# pixel-clock.net
KiCad netlist of a schematic drawn in EAGLE
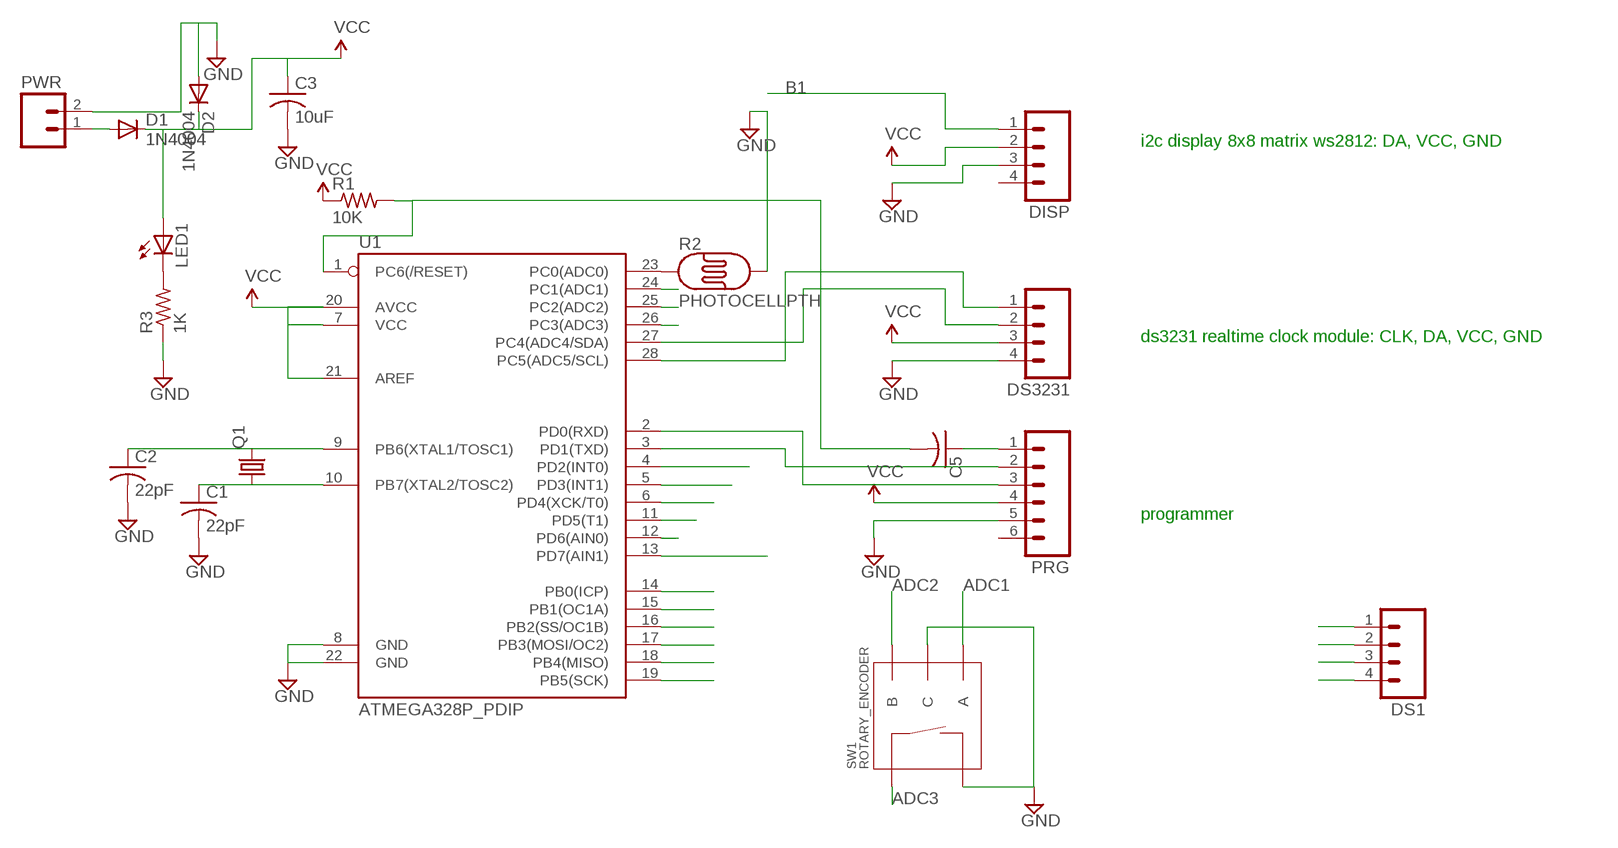
[diagram p0: schematic, sheet 1]

(export (version "E")
  (design (tool "Eeschema 10.0.6"))
  (components
    (comp (ref "C1")
      (value "22pF")
      (footprint "eagle-import:C050-024X044")
      (libsource (lib "eagle-import") (part "C-US050-024X044"))
    )
    (comp (ref "C2")
      (value "22pF")
      (footprint "eagle-import:C050-024X044")
      (libsource (lib "eagle-import") (part "C-US050-024X044"))
    )
    (comp (ref "C3")
      (value "10uF")
      (footprint "eagle-import:C025-025X050")
      (libsource (lib "eagle-import") (part "C-US025-025X050"))
    )
    (comp (ref "C5")
      (value "C-US025-025X050")
      (footprint "eagle-import:C025-025X050")
      (libsource (lib "eagle-import") (part "C-US025-025X050"))
    )
    (comp (ref "D1")
      (value "1N4004")
      (footprint "eagle-import:DO41-10")
      (libsource (lib "eagle-import") (part "1N4004"))
    )
    (comp (ref "D2")
      (value "1N4004")
      (footprint "eagle-import:DO41-10")
      (libsource (lib "eagle-import") (part "1N4004"))
    )
    (comp (ref "DISP")
      (value "M04PTH")
      (footprint "eagle-import:1X04")
      (libsource (lib "eagle-import") (part "M04PTH"))
    )
    (comp (ref "DS1")
      (value "M04PTH")
      (footprint "eagle-import:1X04")
      (libsource (lib "eagle-import") (part "M04PTH"))
    )
    (comp (ref "DS3231")
      (value "M04PTH")
      (footprint "eagle-import:1X04")
      (libsource (lib "eagle-import") (part "M04PTH"))
    )
    (comp (ref "LED1")
      (value "LED3MM")
      (footprint "eagle-import:LED3MM")
      (libsource (lib "eagle-import") (part "LED3MM"))
    )
    (comp (ref "PRG")
      (value "M06SILK_FEMALE_PTH")
      (footprint "eagle-import:1X06")
      (libsource (lib "eagle-import") (part "M06SILK_FEMALE_PTH"))
    )
    (comp (ref "PWR")
      (value "M02PTH3")
      (footprint "eagle-import:1X02_LONGPADS")
      (libsource (lib "eagle-import") (part "M02PTH3"))
    )
    (comp (ref "Q1")
      (value "CRYSTALHC49S")
      (footprint "eagle-import:HC49_S")
      (libsource (lib "eagle-import") (part "CRYSTALHC49S"))
    )
    (comp (ref "R1")
      (value "10K")
      (footprint "eagle-import:0207_9")
      (libsource (lib "eagle-import") (part "R-US_0207/9"))
    )
    (comp (ref "R2")
      (value "PHOTOCELLPTH")
      (footprint "eagle-import:PHOTOCELL")
      (libsource (lib "eagle-import") (part "PHOTOCELLPTH"))
    )
    (comp (ref "R3")
      (value "1K")
      (footprint "eagle-import:0207_9")
      (libsource (lib "eagle-import") (part "R-US_0207/9"))
    )
    (comp (ref "SW1")
      (value "ROTARY_ENCODER")
      (footprint "eagle-import:ROTARY_ENC_PLAIN")
      (libsource (lib "eagle-import") (part "ROTARY_ENCODER"))
    )
    (comp (ref "U1")
      (value "ATMEGA328P_PDIP")
      (footprint "eagle-import:DIL28-3")
      (libsource (lib "eagle-import") (part "ATMEGA328P_PDIP"))
    )
  )
  (nets
    (net (code "1") (name "/ADC1") (class "Default")
      (node (ref "SW1") (pin "A") (pinfunction "A_A") (pintype "bidirectional"))
      (node (ref "U1") (pin "24") (pinfunction "PC1(ADC1)_24") (pintype "bidirectional"))
    )
    (net (code "2") (name "/ADC2") (class "Default")
      (node (ref "SW1") (pin "B") (pinfunction "B_B") (pintype "bidirectional"))
      (node (ref "U1") (pin "25") (pinfunction "PC2(ADC2)_25") (pintype "bidirectional"))
    )
    (net (code "3") (name "/ADC3") (class "Default")
      (node (ref "SW1") (pin "SW+") (pinfunction "SW+_SW+") (pintype "bidirectional"))
      (node (ref "U1") (pin "26") (pinfunction "PC3(ADC3)_26") (pintype "bidirectional"))
    )
    (net (code "4") (name "/B0") (class "Default")
      (node (ref "DS1") (pin "1") (pinfunction "1_1") (pintype "passive"))
      (node (ref "U1") (pin "14") (pinfunction "PB0(ICP)_14") (pintype "bidirectional"))
    )
    (net (code "5") (name "/B1") (class "Default")
      (node (ref "DISP") (pin "1") (pinfunction "1_1") (pintype "passive"))
      (node (ref "U1") (pin "15") (pinfunction "PB1(OC1A)_15") (pintype "bidirectional"))
    )
    (net (code "6") (name "/D6") (class "Default")
      (node (ref "DS1") (pin "3") (pinfunction "3_3") (pintype "passive"))
      (node (ref "U1") (pin "12") (pinfunction "PD6(AIN0)_12") (pintype "bidirectional"))
    )
    (net (code "7") (name "/D7") (class "Default")
      (node (ref "DS1") (pin "2") (pinfunction "2_2") (pintype "passive"))
      (node (ref "U1") (pin "13") (pinfunction "PD7(AIN1)_13") (pintype "bidirectional"))
    )
    (net (code "8") (name "GND") (class "Default")
      (node (ref "C1") (pin "2") (pinfunction "2_2") (pintype "passive"))
      (node (ref "C2") (pin "2") (pinfunction "2_2") (pintype "passive"))
      (node (ref "C3") (pin "2") (pinfunction "2_2") (pintype "passive"))
      (node (ref "D2") (pin "A") (pinfunction "A_A") (pintype "passive"))
      (node (ref "DISP") (pin "3") (pinfunction "3_3") (pintype "passive"))
      (node (ref "DS1") (pin "4") (pinfunction "4_4") (pintype "passive"))
      (node (ref "DS3231") (pin "4") (pinfunction "4_4") (pintype "passive"))
      (node (ref "PRG") (pin "5") (pinfunction "5_5") (pintype "passive"))
      (node (ref "PWR") (pin "2") (pinfunction "2_2") (pintype "passive"))
      (node (ref "R2") (pin "2") (pinfunction "P$2_2") (pintype "bidirectional"))
      (node (ref "R3") (pin "1") (pinfunction "1_1") (pintype "passive"))
      (node (ref "SW1") (pin "C") (pinfunction "C_C") (pintype "bidirectional"))
      (node (ref "SW1") (pin "SW-") (pinfunction "SW-_SW-") (pintype "bidirectional"))
      (node (ref "U1") (pin "22") (pinfunction "GND_22") (pintype "bidirectional"))
      (node (ref "U1") (pin "8") (pinfunction "GND_8") (pintype "bidirectional"))
    )
    (net (code "9") (name "Net-(C5-Pad1)") (class "Default")
      (node (ref "C5") (pin "1") (pinfunction "1_1") (pintype "passive"))
      (node (ref "PRG") (pin "1") (pinfunction "1_1") (pintype "passive"))
    )
    (net (code "10") (name "Net-(D1-PadA)") (class "Default")
      (node (ref "D1") (pin "A") (pinfunction "A_A") (pintype "passive"))
      (node (ref "PWR") (pin "1") (pinfunction "1_1") (pintype "passive"))
    )
    (net (code "11") (name "Net-(LED1-C)") (class "Default")
      (node (ref "LED1") (pin "K") (pinfunction "C_K") (pintype "passive"))
      (node (ref "R3") (pin "2") (pinfunction "2_2") (pintype "passive"))
    )
    (net (code "12") (name "Net-(R2-P$1)") (class "Default")
      (node (ref "R2") (pin "1") (pinfunction "P$1_1") (pintype "bidirectional"))
      (node (ref "U1") (pin "23") (pinfunction "PC0(ADC0)_23") (pintype "bidirectional"))
    )
    (net (code "13") (name "Net-(U1-PB6(XTAL1{slash}TOSC1))") (class "Default")
      (node (ref "C2") (pin "1") (pinfunction "1_1") (pintype "passive"))
      (node (ref "Q1") (pin "2") (pinfunction "2_2") (pintype "passive"))
      (node (ref "U1") (pin "9") (pinfunction "PB6(XTAL1/TOSC1)_9") (pintype "bidirectional"))
    )
    (net (code "14") (name "Net-(U1-PB7(XTAL2{slash}TOSC2))") (class "Default")
      (node (ref "C1") (pin "1") (pinfunction "1_1") (pintype "passive"))
      (node (ref "Q1") (pin "1") (pinfunction "1_1") (pintype "passive"))
      (node (ref "U1") (pin "10") (pinfunction "PB7(XTAL2/TOSC2)_10") (pintype "bidirectional"))
    )
    (net (code "15") (name "Net-(U1-PC4(ADC4{slash}SDA))") (class "Default")
      (node (ref "DS3231") (pin "2") (pinfunction "2_2") (pintype "passive"))
      (node (ref "U1") (pin "27") (pinfunction "PC4(ADC4/SDA)_27") (pintype "bidirectional"))
    )
    (net (code "16") (name "Net-(U1-PC5(ADC5{slash}SCL))") (class "Default")
      (node (ref "DS3231") (pin "1") (pinfunction "1_1") (pintype "passive"))
      (node (ref "U1") (pin "28") (pinfunction "PC5(ADC5/SCL)_28") (pintype "bidirectional"))
    )
    (net (code "17") (name "Net-(U1-PC6({slash}RESET))") (class "Default")
      (node (ref "C5") (pin "2") (pinfunction "2_2") (pintype "passive"))
      (node (ref "R1") (pin "2") (pinfunction "2_2") (pintype "passive"))
      (node (ref "U1") (pin "1") (pinfunction "PC6(/RESET)_1") (pintype "bidirectional"))
    )
    (net (code "18") (name "Net-(U1-PD0(RXD))") (class "Default")
      (node (ref "PRG") (pin "3") (pinfunction "3_3") (pintype "passive"))
      (node (ref "U1") (pin "2") (pinfunction "PD0(RXD)_2") (pintype "bidirectional"))
    )
    (net (code "19") (name "Net-(U1-PD1(TXD))") (class "Default")
      (node (ref "PRG") (pin "2") (pinfunction "2_2") (pintype "passive"))
      (node (ref "U1") (pin "3") (pinfunction "PD1(TXD)_3") (pintype "bidirectional"))
    )
    (net (code "20") (name "VCC") (class "Default")
      (node (ref "C3") (pin "1") (pinfunction "1_1") (pintype "passive"))
      (node (ref "D1") (pin "C") (pinfunction "C_C") (pintype "passive"))
      (node (ref "D2") (pin "C") (pinfunction "C_C") (pintype "passive"))
      (node (ref "DISP") (pin "2") (pinfunction "2_2") (pintype "passive"))
      (node (ref "DS3231") (pin "3") (pinfunction "3_3") (pintype "passive"))
      (node (ref "LED1") (pin "A") (pinfunction "A_A") (pintype "passive"))
      (node (ref "PRG") (pin "4") (pinfunction "4_4") (pintype "passive"))
      (node (ref "R1") (pin "1") (pinfunction "1_1") (pintype "passive"))
      (node (ref "U1") (pin "20") (pinfunction "AVCC_20") (pintype "bidirectional"))
      (node (ref "U1") (pin "21") (pinfunction "AREF_21") (pintype "bidirectional"))
      (node (ref "U1") (pin "7") (pinfunction "VCC_7") (pintype "bidirectional"))
    )
    (net (code "21") (name "unconnected-(DISP-Pad4)") (class "Default")
      (node (ref "DISP") (pin "4") (pinfunction "4_4") (pintype "passive"))
    )
    (net (code "22") (name "unconnected-(PRG-Pad6)") (class "Default")
      (node (ref "PRG") (pin "6") (pinfunction "6_6") (pintype "passive"))
    )
    (net (code "23") (name "unconnected-(U1-PB2(SS{slash}OC1B)-Pad16)") (class "Default")
      (node (ref "U1") (pin "16") (pinfunction "PB2(SS/OC1B)_16") (pintype "bidirectional"))
    )
    (net (code "24") (name "unconnected-(U1-PB3(MOSI{slash}OC2)-Pad17)") (class "Default")
      (node (ref "U1") (pin "17") (pinfunction "PB3(MOSI/OC2)_17") (pintype "bidirectional"))
    )
    (net (code "25") (name "unconnected-(U1-PB4(MISO)-Pad18)") (class "Default")
      (node (ref "U1") (pin "18") (pinfunction "PB4(MISO)_18") (pintype "bidirectional"))
    )
    (net (code "26") (name "unconnected-(U1-PB5(SCK)-Pad19)") (class "Default")
      (node (ref "U1") (pin "19") (pinfunction "PB5(SCK)_19") (pintype "bidirectional"))
    )
    (net (code "27") (name "unconnected-(U1-PD2(INT0)-Pad4)") (class "Default")
      (node (ref "U1") (pin "4") (pinfunction "PD2(INT0)_4") (pintype "bidirectional"))
    )
    (net (code "28") (name "unconnected-(U1-PD3(INT1)-Pad5)") (class "Default")
      (node (ref "U1") (pin "5") (pinfunction "PD3(INT1)_5") (pintype "bidirectional"))
    )
    (net (code "29") (name "unconnected-(U1-PD4(XCK{slash}T0)-Pad6)") (class "Default")
      (node (ref "U1") (pin "6") (pinfunction "PD4(XCK/T0)_6") (pintype "bidirectional"))
    )
    (net (code "30") (name "unconnected-(U1-PD5(T1)-Pad11)") (class "Default")
      (node (ref "U1") (pin "11") (pinfunction "PD5(T1)_11") (pintype "bidirectional"))
    )
  )
)
